# ESC.net
KiCad netlist of a schematic drawn in Altium Designer
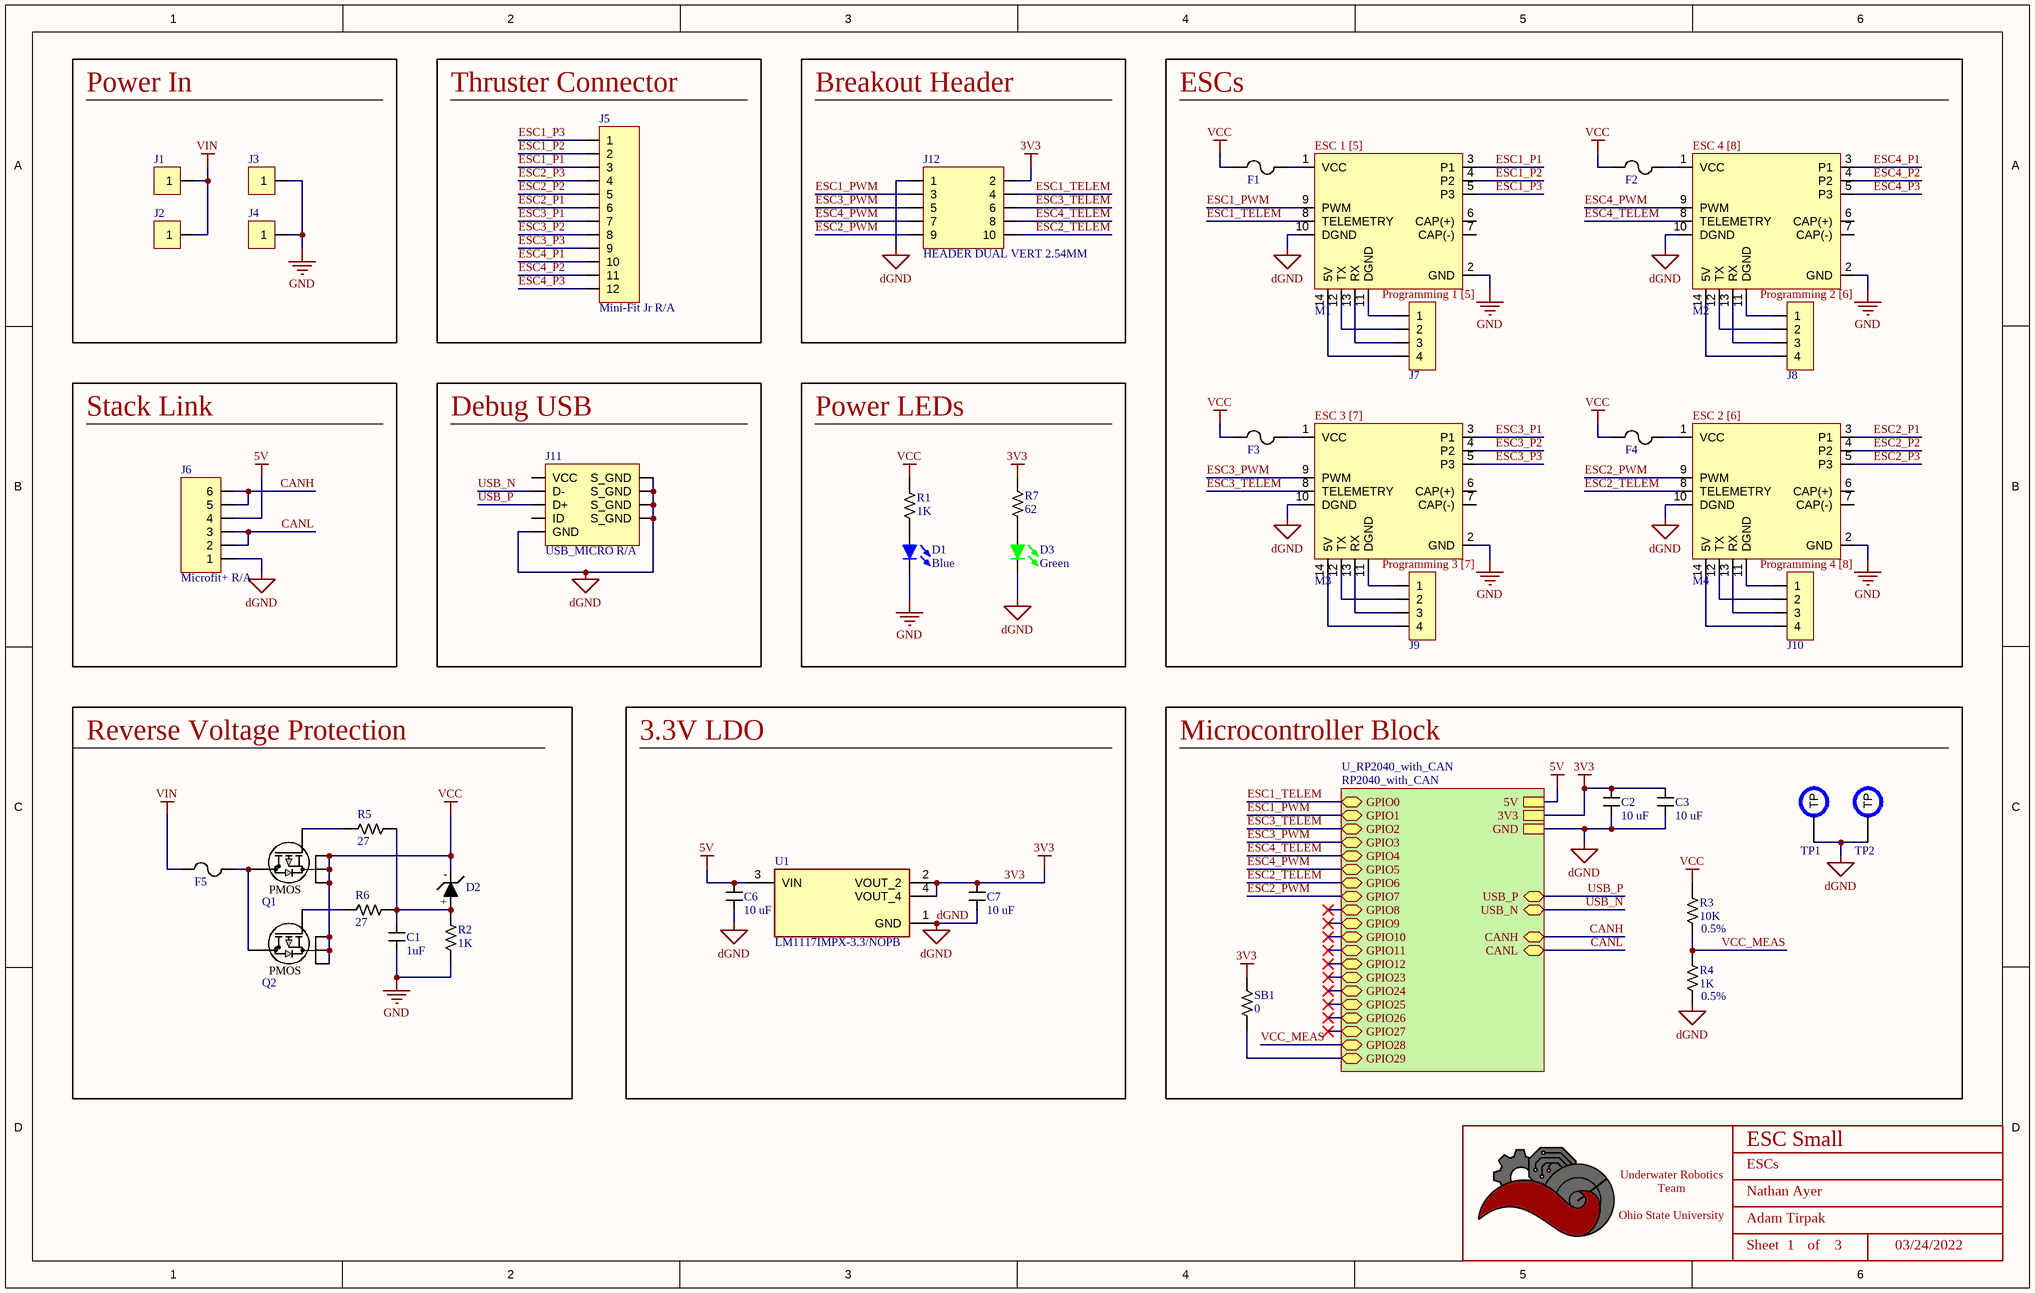
[diagram p0: ESC.SchDoc]

(export (version "E")
  (design (tool "Eeschema 10.0.6"))
  (components
    (comp (ref "*")
      (value "Title_Block")
      (footprint "LOGO")
      (description "UWRT Schematic Title Block Template\r\n\r\nCreated June 2021, Dylan Trainor")
      (libsource (lib "UWRT") (part "Title_Block"))
    )
    (comp (ref "C1")
      (value "1uF")
      (footprint "CAPACITOR_0603")
      (description "Cap 1uF 16V +/-10%\r\nCeramic 0603")
      (fields
        (field (name "TOLERANCE") "+/- 10%")
        (field (name "VOLTAGE") "16V")
        (field (name "MADE BY") "Flip B")
      )
      (libsource (lib "Capacitors") (part "CAPACITOR_1uF_0603"))
    )
    (comp (ref "C2")
      (value "10uF Ceramic 6.3V")
      (footprint "CAPACITOR_0603")
      (description "Cap 10uF 6.3V +/-20%\r\nCeramic 0603")
      (fields
        (field (name "TOLERANCE") "+/- 20%")
        (field (name "VOLTAGE") "6.3V")
        (field (name "VALUE (UF)") "10 uF")
        (field (name "MADE BY") "Flip B")
      )
      (libsource (lib "Capacitors") (part "CAPACITOR_10uF_0603"))
    )
    (comp (ref "C3")
      (value "10uF Ceramic 6.3V")
      (footprint "CAPACITOR_0603")
      (description "Cap 10uF 6.3V +/-20%\r\nCeramic 0603")
      (fields
        (field (name "TOLERANCE") "+/- 20%")
        (field (name "VOLTAGE") "6.3V")
        (field (name "VALUE (UF)") "10 uF")
        (field (name "MADE BY") "Flip B")
      )
      (libsource (lib "Capacitors") (part "CAPACITOR_10uF_0603"))
    )
    (comp (ref "C6")
      (value "10uF Ceramic 6.3V")
      (footprint "CAPACITOR_0603")
      (description "Cap 10uF 6.3V +/-20%\r\nCeramic 0603")
      (fields
        (field (name "TOLERANCE") "+/- 20%")
        (field (name "VOLTAGE") "6.3V")
        (field (name "VALUE (UF)") "10 uF")
        (field (name "MADE BY") "Flip B")
      )
      (libsource (lib "Capacitors") (part "CAPACITOR_10uF_0603"))
    )
    (comp (ref "C7")
      (value "10uF Ceramic 6.3V")
      (footprint "CAPACITOR_0603")
      (description "Cap 10uF 6.3V +/-20%\r\nCeramic 0603")
      (fields
        (field (name "TOLERANCE") "+/- 20%")
        (field (name "VOLTAGE") "6.3V")
        (field (name "VALUE (UF)") "10 uF")
        (field (name "MADE BY") "Flip B")
      )
      (libsource (lib "Capacitors") (part "CAPACITOR_10uF_0603"))
    )
    (comp (ref "D1")
      (value "150060BS75000")
      (footprint "LED_0603")
      (description "LED Blue Vf= 3.2V If = 0.020A\r\n150060BS75000")
      (fields (field (name "COLOR") "Blue") (field (name "MADE BY") "Robert Pafford"))
      (libsource (lib "Diodes") (part "LED_Blue_0603"))
    )
    (comp (ref "D2")
      (value "Zener_Diode_10V_410mW")
      (footprint "SOD-123")
      (description "Zener Diode ¦ 10 V ¦ 410 mW ¦ SOD 123")
      (fields (field (name "POWER") "410mW") (field (name "MADE BY") "Nathan A"))
      (libsource (lib "Diodes") (part "Zener_Diode_10V_410mW"))
    )
    (comp (ref "D3")
      (value "150060GS75000")
      (footprint "LED_0603")
      (description "LED Green Vf= 3.2V If = 0.025A\r\n150060GS75000")
      (fields (field (name "COLOR") "Green") (field (name "MADE BY") "Flip B"))
      (libsource (lib "Diodes") (part "LED_Green_0603_3.2V"))
    )
    (comp (ref "F1")
      (value "0685H9150-01")
      (footprint "0501Series_LTF")
      (description "Bel Fuse  ¦ 15A ¦ 32V DC ¦ SMD ¦ Fast Blow ¦ 1206")
      (fields (field (name "CREATED BY") "Nathan Ayer"))
      (libsource (lib "Fuses") (part "Bel Fuse 15A"))
    )
    (comp (ref "F2")
      (value "0685H9150-01")
      (footprint "0501Series_LTF")
      (description "Bel Fuse  ¦ 15A ¦ 32V DC ¦ SMD ¦ Fast Blow ¦ 1206")
      (fields (field (name "CREATED BY") "Nathan Ayer"))
      (libsource (lib "Fuses") (part "Bel Fuse 15A"))
    )
    (comp (ref "F3")
      (value "0685H9150-01")
      (footprint "0501Series_LTF")
      (description "Bel Fuse  ¦ 15A ¦ 32V DC ¦ SMD ¦ Fast Blow ¦ 1206")
      (fields (field (name "CREATED BY") "Nathan Ayer"))
      (libsource (lib "Fuses") (part "Bel Fuse 15A"))
    )
    (comp (ref "F4")
      (value "0685H9150-01")
      (footprint "0501Series_LTF")
      (description "Bel Fuse  ¦ 15A ¦ 32V DC ¦ SMD ¦ Fast Blow ¦ 1206")
      (fields (field (name "CREATED BY") "Nathan Ayer"))
      (libsource (lib "Fuses") (part "Bel Fuse 15A"))
    )
    (comp (ref "F5")
      (value "1245HC60-RTR")
      (footprint "2-SMD Fuse")
      (description "Eaton  ¦ 60A ¦ 80V DC ¦ SMD ¦ Fast Blow ¦ 2-SMD")
      (fields (field (name "CREATED BY") "Nathan Ayer"))
      (libsource (lib "Fuses") (part "Eaton 60A Fuse"))
    )
    (comp (ref "J1")
      (value "Redcube M4 Term 85A")
      (footprint "Redcube M4 Term 85A")
      (fields (field (name "CREATED BY") "Nahtan Ayer"))
      (libsource (lib "Connectors") (part "Redcube M4 Term 85A"))
    )
    (comp (ref "J2")
      (value "Redcube M4 Term 85A")
      (footprint "Redcube M4 Term 85A")
      (fields (field (name "CREATED BY") "Nahtan Ayer"))
      (libsource (lib "Connectors") (part "Redcube M4 Term 85A"))
    )
    (comp (ref "J3")
      (value "Redcube M4 Term 85A")
      (footprint "Redcube M4 Term 85A")
      (fields (field (name "CREATED BY") "Nahtan Ayer"))
      (libsource (lib "Connectors") (part "Redcube M4 Term 85A"))
    )
    (comp (ref "J4")
      (value "Redcube M4 Term 85A")
      (footprint "Redcube M4 Term 85A")
      (fields (field (name "CREATED BY") "Nahtan Ayer"))
      (libsource (lib "Connectors") (part "Redcube M4 Term 85A"))
    )
    (comp (ref "J5")
      (value "Mini-Fit Jr R/A")
      (footprint "CONN_MOLEX_MINIFIT JR_12 POS_R/A")
      (description "Molex Minifit Jr. 5569 \r\n12 Pos R/A Natural")
      (fields (field (name "MANUFACTURER") "Molex") (field (name "CREATED BY") "Flip B"))
      (libsource (lib "Connectors") (part "CONN_MOLEX_MINIFIT JR_12POS_R/A"))
    )
    (comp (ref "J6")
      (value "Microfit+ R/A")
      (footprint "CONN_MOLEX_MICROFIT+_6_POS_R/A")
      (description "Molex Microfit+ \r\n212528 6 POS R/A Black")
      (fields (field (name "MANUFACTURER") "Molex"))
      (libsource (lib "Connectors") (part "CONN_MOLEX_MICROFIT+_6POS_R/A"))
    )
    (comp (ref "J7")
      (value "HEADER VERT 2.54MM")
      (footprint "HEADER_4PIN_2.54MM")
      (description "CONN HEADER VERT 4POS 2.54MM")
      (fields (field (name "MADE BY") "Robert Pafford"))
      (libsource (lib "Connectors") (part "HEADER_4PIN_2.54MM"))
    )
    (comp (ref "J8")
      (value "HEADER VERT 2.54MM")
      (footprint "HEADER_4PIN_2.54MM")
      (description "CONN HEADER VERT 4POS 2.54MM")
      (fields (field (name "MADE BY") "Robert Pafford"))
      (libsource (lib "Connectors") (part "HEADER_4PIN_2.54MM"))
    )
    (comp (ref "J9")
      (value "HEADER VERT 2.54MM")
      (footprint "HEADER_4PIN_2.54MM")
      (description "CONN HEADER VERT 4POS 2.54MM")
      (fields (field (name "MADE BY") "Robert Pafford"))
      (libsource (lib "Connectors") (part "HEADER_4PIN_2.54MM"))
    )
    (comp (ref "J10")
      (value "HEADER VERT 2.54MM")
      (footprint "HEADER_4PIN_2.54MM")
      (description "CONN HEADER VERT 4POS 2.54MM")
      (fields (field (name "MADE BY") "Robert Pafford"))
      (libsource (lib "Connectors") (part "HEADER_4PIN_2.54MM"))
    )
    (comp (ref "J11")
      (value "USB_MICRO R/A")
      (footprint "CONN_MINIUSB")
      (description "Amphenol Micro USB-B\r\nUSB2.0 5 Pin Right Angle SMD")
      (fields (field (name "MANUFACTURER") "Amphenol") (field (name "CREATED BY") "Flip B"))
      (libsource (lib "Connectors") (part "CONN_MICROUSB"))
    )
    (comp (ref "J12")
      (value "HEADER DUAL VERT 2.54MM")
      (footprint "HEADER_2X5PIN_2.54MM")
      (description "CONN HEADER VERT 10POS 2.54MM")
      (fields (field (name "MADE BY") "Robert Pafford"))
      (libsource (lib "Connectors") (part "HEADER_2x5PIN_2.54MM"))
    )
    (comp (ref "M1")
      (value "APD 80F3[X]")
      (footprint "APD 80F3[X]")
      (description "Advanced Power Drives 80F3[X] ESC ¦ 15-35V ¦ 80A")
      (fields
        (field (name "VOLTAGE") "15-35V")
        (field (name "MANUFACTURER") "Advanced Power Drives")
        (field (name "CREATED BY") "Nathan Ayer")
      )
      (libsource (lib "Modules") (part "APD 80F3[X]"))
    )
    (comp (ref "M2")
      (value "APD 80F3[X]")
      (footprint "APD 80F3[X]")
      (description "Advanced Power Drives 80F3[X] ESC ¦ 15-35V ¦ 80A")
      (fields
        (field (name "VOLTAGE") "15-35V")
        (field (name "MANUFACTURER") "Advanced Power Drives")
        (field (name "CREATED BY") "Nathan Ayer")
      )
      (libsource (lib "Modules") (part "APD 80F3[X]"))
    )
    (comp (ref "M3")
      (value "APD 80F3[X]")
      (footprint "APD 80F3[X]")
      (description "Advanced Power Drives 80F3[X] ESC ¦ 15-35V ¦ 80A")
      (fields
        (field (name "VOLTAGE") "15-35V")
        (field (name "MANUFACTURER") "Advanced Power Drives")
        (field (name "CREATED BY") "Nathan Ayer")
      )
      (libsource (lib "Modules") (part "APD 80F3[X]"))
    )
    (comp (ref "M4")
      (value "APD 80F3[X]")
      (footprint "APD 80F3[X]")
      (description "Advanced Power Drives 80F3[X] ESC ¦ 15-35V ¦ 80A")
      (fields
        (field (name "VOLTAGE") "15-35V")
        (field (name "MANUFACTURER") "Advanced Power Drives")
        (field (name "CREATED BY") "Nathan Ayer")
      )
      (libsource (lib "Modules") (part "APD 80F3[X]"))
    )
    (comp (ref "Q1")
      (value "MOSFET P-Ch 30V 60A SO-8")
      (footprint "MOSFET_7DP-T1-GE3_VIS")
      (description "P-Channel 30 V 60A (Tc) 65.8W (Tc) Surface Mount PowerPAK® SO-8")
      (fields
        (field (name "MANUFACTURER_PART_NUMBER") "SIR167DP-T1-GE3")
        (field (name "COPYRIGHT") "Copyright (C) 2022 Ultra Librarian. All rights reserved.")
      )
      (libsource (lib "Transistors") (part "SIR167DP-T1-GE3"))
    )
    (comp (ref "Q2")
      (value "MOSFET P-Ch 30V 60A SO-8")
      (footprint "MOSFET_7DP-T1-GE3_VIS")
      (description "P-Channel 30 V 60A (Tc) 65.8W (Tc) Surface Mount PowerPAK® SO-8")
      (fields
        (field (name "MANUFACTURER_PART_NUMBER") "SIR167DP-T1-GE3")
        (field (name "COPYRIGHT") "Copyright (C) 2022 Ultra Librarian. All rights reserved.")
      )
      (libsource (lib "Transistors") (part "SIR167DP-T1-GE3"))
    )
    (comp (ref "R1")
      (value "1k Ohm 5% 1/8W")
      (footprint "RESISTOR_0603")
      (description "RES 1k OHM 5% 1/8W 0603")
      (fields
        (field (name "TOLERANCE") "+/- 5%")
        (field (name "VALUE  (OHMS)") "1K")
        (field (name "MADE BY") "Robert Pafford")
      )
      (libsource (lib "Resistors") (part "RESISTOR_1K_0603"))
    )
    (comp (ref "R2")
      (value "1k Ohm 5% 1/8W")
      (footprint "RESISTOR_0603")
      (description "RES 1k OHM 5% 1/8W 0603")
      (fields
        (field (name "TOLERANCE") "+/- 5%")
        (field (name "VALUE  (OHMS)") "1K")
        (field (name "MADE BY") "Robert Pafford")
      )
      (libsource (lib "Resistors") (part "RESISTOR_1K_0603"))
    )
    (comp (ref "R3")
      (value "10k Ohm 0.5% 1/10W")
      (footprint "RESISTOR_0603")
      (description "RES 10k OHM 0.5% 1/10W 0603")
      (fields
        (field (name "TOLERANCE") "+/- 0.5%")
        (field (name "VALUE  (OHMS)") "10K")
        (field (name "MADE BY") "Robert Pafford")
      )
      (libsource (lib "Resistors") (part "RESISTOR_10K_0.5%_0603"))
    )
    (comp (ref "R4")
      (value "1k Ohm 5% 1/10W")
      (footprint "RESISTOR_0603")
      (description "RES 1k OHM 0.5% 1/10W 0603")
      (fields
        (field (name "TOLERANCE") "+/- 0.5%")
        (field (name "VALUE  (OHMS)") "1K")
        (field (name "MADE BY") "Robert Pafford")
      )
      (libsource (lib "Resistors") (part "RESISTOR_1K_0.5%_0603"))
    )
    (comp (ref "R5")
      (value "27 Ohm 5% 1/8W")
      (footprint "RESISTOR_0603")
      (description "RES 27 OHM 5% 1/8W 0603")
      (fields
        (field (name "TOLERANCE") "+/- 5%")
        (field (name "VALUE  (OHMS)") "27")
        (field (name "MADE BY") "Robert Pafford")
      )
      (libsource (lib "Resistors") (part "RESISTOR_27_0603"))
    )
    (comp (ref "R6")
      (value "27 Ohm 5% 1/8W")
      (footprint "RESISTOR_0603")
      (description "RES 27 OHM 5% 1/8W 0603")
      (fields
        (field (name "TOLERANCE") "+/- 5%")
        (field (name "VALUE  (OHMS)") "27")
        (field (name "MADE BY") "Robert Pafford")
      )
      (libsource (lib "Resistors") (part "RESISTOR_27_0603"))
    )
    (comp (ref "R7")
      (value "62 Ohm 1% 1/4W")
      (footprint "RESISTOR_0603")
      (description "RES SMD 62 OHM 1% 1/4W 0603")
      (fields
        (field (name "TOLERANCE") "+/- 1%")
        (field (name "VALUE  (OHMS)") "62")
        (field (name "MADE BY") "Robert Pafford")
      )
      (libsource (lib "Resistors") (part "RESISTOR_62_0603"))
    )
    (comp (ref "SB1")
      (value "0 Ohm Jumper No Fit")
      (footprint "RESISTOR_0603")
      (description "0 Ohm Jumper No Fit for Solder Bridge")
      (fields (field (name "VALUE  (OHMS)") "0") (field (name "MADE BY") "Robert Pafford"))
      (libsource (lib "Resistors") (part "JUMPER_0_0603"))
    )
    (comp (ref "TP1")
      (value "PCB Test Point")
      (footprint "TESTPOINT_1.2MM")
      (fields (field (name "MADE BY") "Robert Pafford"))
      (libsource (lib "Connectors") (part "TESTPOINT"))
    )
    (comp (ref "TP2")
      (value "PCB Test Point")
      (footprint "TESTPOINT_1.2MM")
      (fields (field (name "MADE BY") "Robert Pafford"))
      (libsource (lib "Connectors") (part "TESTPOINT"))
    )
    (comp (ref "U1")
      (value "LM1117IMPX-3.3/NOPB")
      (footprint "SOT-223-4")
      (description "800-mA 15-V linear voltage regulator 4-SOT-223 -40 to 125")
      (fields (field (name "MF") "Texas Instruments"))
      (libsource (lib "Integrated Circuits") (part "LM1117IMPX-3.3/NOPB"))
    )
  )
  (nets
    (net (code "1") (name "/CANH") (class "Default")
      (node (ref "J6") (pin "5") (pinfunction "5_5") (pintype "passive"))
      (node (ref "J6") (pin "6") (pinfunction "6_6") (pintype "passive"))
    )
    (net (code "2") (name "/CANL") (class "Default")
      (node (ref "J6") (pin "2") (pinfunction "2_2") (pintype "passive"))
      (node (ref "J6") (pin "3") (pinfunction "3_3") (pintype "passive"))
    )
    (net (code "3") (name "/ESC1_P1") (class "Default")
      (node (ref "J5") (pin "3") (pinfunction "3_3") (pintype "passive"))
      (node (ref "M1") (pin "3") (pinfunction "P1_3") (pintype "passive"))
    )
    (net (code "4") (name "/ESC1_P2") (class "Default")
      (node (ref "J5") (pin "2") (pinfunction "2_2") (pintype "passive"))
      (node (ref "M1") (pin "4") (pinfunction "P2_4") (pintype "passive"))
    )
    (net (code "5") (name "/ESC1_P3") (class "Default")
      (node (ref "J5") (pin "1") (pinfunction "1_1") (pintype "passive"))
      (node (ref "M1") (pin "5") (pinfunction "P3_5") (pintype "passive"))
    )
    (net (code "6") (name "/ESC1_PWM") (class "Default")
      (node (ref "J12") (pin "3") (pinfunction "3_3") (pintype "passive"))
      (node (ref "M1") (pin "9") (pinfunction "PWM_9") (pintype "passive"))
    )
    (net (code "7") (name "/ESC1_TELEM") (class "Default")
      (node (ref "J12") (pin "4") (pinfunction "4_4") (pintype "passive"))
      (node (ref "M1") (pin "8") (pinfunction "TELEMETRY_8") (pintype "passive"))
    )
    (net (code "8") (name "/ESC2_P1") (class "Default")
      (node (ref "J5") (pin "6") (pinfunction "6_6") (pintype "passive"))
      (node (ref "M4") (pin "3") (pinfunction "P1_3") (pintype "passive"))
    )
    (net (code "9") (name "/ESC2_P2") (class "Default")
      (node (ref "J5") (pin "5") (pinfunction "5_5") (pintype "passive"))
      (node (ref "M4") (pin "4") (pinfunction "P2_4") (pintype "passive"))
    )
    (net (code "10") (name "/ESC2_P3") (class "Default")
      (node (ref "J5") (pin "4") (pinfunction "4_4") (pintype "passive"))
      (node (ref "M4") (pin "5") (pinfunction "P3_5") (pintype "passive"))
    )
    (net (code "11") (name "/ESC2_PWM") (class "Default")
      (node (ref "J12") (pin "9") (pinfunction "9_9") (pintype "passive"))
      (node (ref "M4") (pin "9") (pinfunction "PWM_9") (pintype "passive"))
    )
    (net (code "12") (name "/ESC2_TELEM") (class "Default")
      (node (ref "J12") (pin "10") (pinfunction "10_10") (pintype "passive"))
      (node (ref "M4") (pin "8") (pinfunction "TELEMETRY_8") (pintype "passive"))
    )
    (net (code "13") (name "/ESC3_P1") (class "Default")
      (node (ref "J5") (pin "7") (pinfunction "7_7") (pintype "passive"))
      (node (ref "M3") (pin "3") (pinfunction "P1_3") (pintype "passive"))
    )
    (net (code "14") (name "/ESC3_P2") (class "Default")
      (node (ref "J5") (pin "8") (pinfunction "8_8") (pintype "passive"))
      (node (ref "M3") (pin "4") (pinfunction "P2_4") (pintype "passive"))
    )
    (net (code "15") (name "/ESC3_P3") (class "Default")
      (node (ref "J5") (pin "9") (pinfunction "9_9") (pintype "passive"))
      (node (ref "M3") (pin "5") (pinfunction "P3_5") (pintype "passive"))
    )
    (net (code "16") (name "/ESC3_PWM") (class "Default")
      (node (ref "J12") (pin "5") (pinfunction "5_5") (pintype "passive"))
      (node (ref "M3") (pin "9") (pinfunction "PWM_9") (pintype "passive"))
    )
    (net (code "17") (name "/ESC3_TELEM") (class "Default")
      (node (ref "J12") (pin "6") (pinfunction "6_6") (pintype "passive"))
      (node (ref "M3") (pin "8") (pinfunction "TELEMETRY_8") (pintype "passive"))
    )
    (net (code "18") (name "/ESC4_P1") (class "Default")
      (node (ref "J5") (pin "10") (pinfunction "10_10") (pintype "passive"))
      (node (ref "M2") (pin "3") (pinfunction "P1_3") (pintype "passive"))
    )
    (net (code "19") (name "/ESC4_P2") (class "Default")
      (node (ref "J5") (pin "11") (pinfunction "11_11") (pintype "passive"))
      (node (ref "M2") (pin "4") (pinfunction "P2_4") (pintype "passive"))
    )
    (net (code "20") (name "/ESC4_P3") (class "Default")
      (node (ref "J5") (pin "12") (pinfunction "12_12") (pintype "passive"))
      (node (ref "M2") (pin "5") (pinfunction "P3_5") (pintype "passive"))
    )
    (net (code "21") (name "/ESC4_PWM") (class "Default")
      (node (ref "J12") (pin "7") (pinfunction "7_7") (pintype "passive"))
      (node (ref "M2") (pin "9") (pinfunction "PWM_9") (pintype "passive"))
    )
    (net (code "22") (name "/ESC4_TELEM") (class "Default")
      (node (ref "J12") (pin "8") (pinfunction "8_8") (pintype "passive"))
      (node (ref "M2") (pin "8") (pinfunction "TELEMETRY_8") (pintype "passive"))
    )
    (net (code "33") (name "/GPIO29") (class "Default")
      (node (ref "SB1") (pin "1") (pinfunction "1_1") (pintype "passive"))
    )
    (net (code "34") (name "/USB_N") (class "Default")
      (node (ref "J11") (pin "2") (pinfunction "D-_2") (pintype "passive"))
    )
    (net (code "35") (name "/USB_P") (class "Default")
      (node (ref "J11") (pin "3") (pinfunction "D+_3") (pintype "passive"))
    )
    (net (code "36") (name "/VCC_MEAS") (class "Default")
      (node (ref "R3") (pin "2") (pinfunction "2_2") (pintype "passive"))
      (node (ref "R4") (pin "1") (pinfunction "1_1") (pintype "passive"))
    )
    (net (code "37") (name "3V3") (class "Default")
      (node (ref "C2") (pin "1") (pinfunction "1_1") (pintype "passive"))
      (node (ref "C3") (pin "1") (pinfunction "1_1") (pintype "passive"))
      (node (ref "C7") (pin "1") (pinfunction "1_1") (pintype "passive"))
      (node (ref "J12") (pin "2") (pinfunction "2_2") (pintype "passive"))
      (node (ref "R7") (pin "2") (pinfunction "2_2") (pintype "passive"))
      (node (ref "SB1") (pin "2") (pinfunction "2_2") (pintype "passive"))
      (node (ref "U1") (pin "2") (pinfunction "VOUT_2_2") (pintype "power_in"))
      (node (ref "U1") (pin "4") (pinfunction "VOUT_4_4") (pintype "power_in"))
    )
    (net (code "38") (name "5V") (class "Default")
      (node (ref "C6") (pin "1") (pinfunction "1_1") (pintype "passive"))
      (node (ref "J6") (pin "4") (pinfunction "4_4") (pintype "passive"))
      (node (ref "U1") (pin "3") (pinfunction "VIN_3") (pintype "power_in"))
    )
    (net (code "39") (name "GND") (class "Default")
      (node (ref "C1") (pin "1") (pinfunction "1_1") (pintype "passive"))
      (node (ref "D1") (pin "2") (pinfunction "2_2") (pintype "passive"))
      (node (ref "J3") (pin "1") (pinfunction "1_1") (pintype "passive"))
      (node (ref "J4") (pin "1") (pinfunction "1_1") (pintype "passive"))
      (node (ref "M1") (pin "2") (pinfunction "GND_2") (pintype "passive"))
      (node (ref "M2") (pin "2") (pinfunction "GND_2") (pintype "passive"))
      (node (ref "M3") (pin "2") (pinfunction "GND_2") (pintype "passive"))
      (node (ref "M4") (pin "2") (pinfunction "GND_2") (pintype "passive"))
      (node (ref "R2") (pin "2") (pinfunction "2_2") (pintype "passive"))
    )
    (net (code "40") (name "Net-(C1-Pad2)") (class "Default")
      (node (ref "C1") (pin "2") (pinfunction "2_2") (pintype "passive"))
      (node (ref "D2") (pin "1") (pinfunction "1_1") (pintype "passive"))
      (node (ref "R2") (pin "1") (pinfunction "1_1") (pintype "passive"))
      (node (ref "R5") (pin "2") (pinfunction "2_2") (pintype "passive"))
      (node (ref "R6") (pin "1") (pinfunction "1_1") (pintype "passive"))
    )
    (net (code "41") (name "Net-(D1-Pad1)") (class "Default")
      (node (ref "D1") (pin "1") (pinfunction "1_1") (pintype "passive"))
      (node (ref "R1") (pin "2") (pinfunction "2_2") (pintype "passive"))
    )
    (net (code "42") (name "Net-(D3-Pad1)") (class "Default")
      (node (ref "D3") (pin "1") (pinfunction "1_1") (pintype "passive"))
      (node (ref "R7") (pin "1") (pinfunction "1_1") (pintype "passive"))
    )
    (net (code "43") (name "Net-(F5-Pad2)") (class "Default")
      (node (ref "F5") (pin "2") (pinfunction "2_2") (pintype "passive"))
      (node (ref "Q1") (pin "D") (pinfunction "D_D") (pintype "passive"))
      (node (ref "Q2") (pin "D") (pinfunction "D_D") (pintype "passive"))
    )
    (net (code "44") (name "Net-(J7-Pad1)") (class "Default")
      (node (ref "J7") (pin "1") (pinfunction "1_1") (pintype "passive"))
      (node (ref "M1") (pin "11") (pinfunction "DGND_11") (pintype "passive"))
    )
    (net (code "45") (name "Net-(J8-Pad1)") (class "Default")
      (node (ref "J8") (pin "1") (pinfunction "1_1") (pintype "passive"))
      (node (ref "M2") (pin "11") (pinfunction "DGND_11") (pintype "passive"))
    )
    (net (code "46") (name "Net-(J9-Pad1)") (class "Default")
      (node (ref "J9") (pin "1") (pinfunction "1_1") (pintype "passive"))
      (node (ref "M3") (pin "11") (pinfunction "DGND_11") (pintype "passive"))
    )
    (net (code "47") (name "Net-(J10-Pad1)") (class "Default")
      (node (ref "J10") (pin "1") (pinfunction "1_1") (pintype "passive"))
      (node (ref "M4") (pin "11") (pinfunction "DGND_11") (pintype "passive"))
    )
    (net (code "48") (name "Net-(M1-5V)") (class "Default")
      (node (ref "J7") (pin "4") (pinfunction "4_4") (pintype "passive"))
      (node (ref "M1") (pin "14") (pinfunction "5V_14") (pintype "passive"))
    )
    (net (code "49") (name "Net-(M1-RX)") (class "Default")
      (node (ref "J7") (pin "3") (pinfunction "3_3") (pintype "passive"))
      (node (ref "M1") (pin "13") (pinfunction "RX_13") (pintype "passive"))
    )
    (net (code "50") (name "Net-(M1-TX)") (class "Default")
      (node (ref "J7") (pin "2") (pinfunction "2_2") (pintype "passive"))
      (node (ref "M1") (pin "12") (pinfunction "TX_12") (pintype "passive"))
    )
    (net (code "51") (name "Net-(M1-VCC)") (class "Default")
      (node (ref "F1") (pin "2") (pinfunction "2_2") (pintype "passive"))
      (node (ref "M1") (pin "1") (pinfunction "VCC_1") (pintype "passive"))
    )
    (net (code "52") (name "Net-(M2-5V)") (class "Default")
      (node (ref "J8") (pin "4") (pinfunction "4_4") (pintype "passive"))
      (node (ref "M2") (pin "14") (pinfunction "5V_14") (pintype "passive"))
    )
    (net (code "53") (name "Net-(M2-RX)") (class "Default")
      (node (ref "J8") (pin "3") (pinfunction "3_3") (pintype "passive"))
      (node (ref "M2") (pin "13") (pinfunction "RX_13") (pintype "passive"))
    )
    (net (code "54") (name "Net-(M2-TX)") (class "Default")
      (node (ref "J8") (pin "2") (pinfunction "2_2") (pintype "passive"))
      (node (ref "M2") (pin "12") (pinfunction "TX_12") (pintype "passive"))
    )
    (net (code "55") (name "Net-(M2-VCC)") (class "Default")
      (node (ref "F2") (pin "2") (pinfunction "2_2") (pintype "passive"))
      (node (ref "M2") (pin "1") (pinfunction "VCC_1") (pintype "passive"))
    )
    (net (code "56") (name "Net-(M3-5V)") (class "Default")
      (node (ref "J9") (pin "4") (pinfunction "4_4") (pintype "passive"))
      (node (ref "M3") (pin "14") (pinfunction "5V_14") (pintype "passive"))
    )
    (net (code "57") (name "Net-(M3-RX)") (class "Default")
      (node (ref "J9") (pin "3") (pinfunction "3_3") (pintype "passive"))
      (node (ref "M3") (pin "13") (pinfunction "RX_13") (pintype "passive"))
    )
    (net (code "58") (name "Net-(M3-TX)") (class "Default")
      (node (ref "J9") (pin "2") (pinfunction "2_2") (pintype "passive"))
      (node (ref "M3") (pin "12") (pinfunction "TX_12") (pintype "passive"))
    )
    (net (code "59") (name "Net-(M3-VCC)") (class "Default")
      (node (ref "F3") (pin "2") (pinfunction "2_2") (pintype "passive"))
      (node (ref "M3") (pin "1") (pinfunction "VCC_1") (pintype "passive"))
    )
    (net (code "60") (name "Net-(M4-5V)") (class "Default")
      (node (ref "J10") (pin "4") (pinfunction "4_4") (pintype "passive"))
      (node (ref "M4") (pin "14") (pinfunction "5V_14") (pintype "passive"))
    )
    (net (code "61") (name "Net-(M4-RX)") (class "Default")
      (node (ref "J10") (pin "3") (pinfunction "3_3") (pintype "passive"))
      (node (ref "M4") (pin "13") (pinfunction "RX_13") (pintype "passive"))
    )
    (net (code "62") (name "Net-(M4-TX)") (class "Default")
      (node (ref "J10") (pin "2") (pinfunction "2_2") (pintype "passive"))
      (node (ref "M4") (pin "12") (pinfunction "TX_12") (pintype "passive"))
    )
    (net (code "63") (name "Net-(M4-VCC)") (class "Default")
      (node (ref "F4") (pin "2") (pinfunction "2_2") (pintype "passive"))
      (node (ref "M4") (pin "1") (pinfunction "VCC_1") (pintype "passive"))
    )
    (net (code "64") (name "Net-(Q1-G)") (class "Default")
      (node (ref "Q1") (pin "4") (pinfunction "G_4") (pintype "passive"))
      (node (ref "R5") (pin "1") (pinfunction "1_1") (pintype "passive"))
    )
    (net (code "65") (name "Net-(Q2-G)") (class "Default")
      (node (ref "Q2") (pin "4") (pinfunction "G_4") (pintype "passive"))
      (node (ref "R6") (pin "2") (pinfunction "2_2") (pintype "passive"))
    )
    (net (code "66") (name "VCC") (class "Default")
      (node (ref "D2") (pin "2") (pinfunction "2_2") (pintype "passive"))
      (node (ref "F1") (pin "1") (pinfunction "1_1") (pintype "passive"))
      (node (ref "F2") (pin "1") (pinfunction "1_1") (pintype "passive"))
      (node (ref "F3") (pin "1") (pinfunction "1_1") (pintype "passive"))
      (node (ref "F4") (pin "1") (pinfunction "1_1") (pintype "passive"))
      (node (ref "Q1") (pin "1") (pinfunction "S_1") (pintype "passive"))
      (node (ref "Q1") (pin "2") (pinfunction "S_2") (pintype "passive"))
      (node (ref "Q1") (pin "3") (pinfunction "S_3") (pintype "passive"))
      (node (ref "Q2") (pin "1") (pinfunction "S_1") (pintype "passive"))
      (node (ref "Q2") (pin "2") (pinfunction "S_2") (pintype "passive"))
      (node (ref "Q2") (pin "3") (pinfunction "S_3") (pintype "passive"))
      (node (ref "R1") (pin "1") (pinfunction "1_1") (pintype "passive"))
      (node (ref "R3") (pin "1") (pinfunction "1_1") (pintype "passive"))
    )
    (net (code "67") (name "VIN") (class "Default")
      (node (ref "F5") (pin "1") (pinfunction "1_1") (pintype "passive"))
      (node (ref "J1") (pin "1") (pinfunction "1_1") (pintype "passive"))
      (node (ref "J2") (pin "1") (pinfunction "1_1") (pintype "passive"))
    )
    (net (code "68") (name "dGND") (class "Default")
      (node (ref "C2") (pin "2") (pinfunction "2_2") (pintype "passive"))
      (node (ref "C3") (pin "2") (pinfunction "2_2") (pintype "passive"))
      (node (ref "C6") (pin "2") (pinfunction "2_2") (pintype "passive"))
      (node (ref "C7") (pin "2") (pinfunction "2_2") (pintype "passive"))
      (node (ref "D3") (pin "2") (pinfunction "2_2") (pintype "passive"))
      (node (ref "J11") (pin "5") (pinfunction "GND_5") (pintype "passive"))
      (node (ref "J11") (pin "6") (pinfunction "S_GND_6") (pintype "passive"))
      (node (ref "J11") (pin "7") (pinfunction "S_GND_7") (pintype "passive"))
      (node (ref "J11") (pin "8") (pinfunction "S_GND_8") (pintype "passive"))
      (node (ref "J11") (pin "9") (pinfunction "S_GND_9") (pintype "passive"))
      (node (ref "J12") (pin "1") (pinfunction "1_1") (pintype "passive"))
      (node (ref "J6") (pin "1") (pinfunction "1_1") (pintype "passive"))
      (node (ref "M1") (pin "10") (pinfunction "DGND_10") (pintype "passive"))
      (node (ref "M2") (pin "10") (pinfunction "DGND_10") (pintype "passive"))
      (node (ref "M3") (pin "10") (pinfunction "DGND_10") (pintype "passive"))
      (node (ref "M4") (pin "10") (pinfunction "DGND_10") (pintype "passive"))
      (node (ref "R4") (pin "2") (pinfunction "2_2") (pintype "passive"))
      (node (ref "TP1") (pin "TP") (pinfunction "TP_TP") (pintype "passive"))
      (node (ref "TP2") (pin "TP") (pinfunction "TP_TP") (pintype "passive"))
      (node (ref "U1") (pin "1") (pinfunction "GND_1") (pintype "power_in"))
    )
    (net (code "69") (name "unconnected-(J11-ID-Pad4)") (class "Default")
      (node (ref "J11") (pin "4") (pinfunction "ID_4") (pintype "passive"))
    )
    (net (code "70") (name "unconnected-(J11-VCC-Pad1)") (class "Default")
      (node (ref "J11") (pin "1") (pinfunction "VCC_1") (pintype "passive"))
    )
    (net (code "71") (name "unconnected-(M1-CAP(+)-Pad6)") (class "Default")
      (node (ref "M1") (pin "6") (pinfunction "CAP(+)_6") (pintype "passive"))
    )
    (net (code "72") (name "unconnected-(M1-CAP(-)-Pad7)") (class "Default")
      (node (ref "M1") (pin "7") (pinfunction "CAP(-)_7") (pintype "passive"))
    )
    (net (code "73") (name "unconnected-(M2-CAP(+)-Pad6)") (class "Default")
      (node (ref "M2") (pin "6") (pinfunction "CAP(+)_6") (pintype "passive"))
    )
    (net (code "74") (name "unconnected-(M2-CAP(-)-Pad7)") (class "Default")
      (node (ref "M2") (pin "7") (pinfunction "CAP(-)_7") (pintype "passive"))
    )
    (net (code "75") (name "unconnected-(M3-CAP(+)-Pad6)") (class "Default")
      (node (ref "M3") (pin "6") (pinfunction "CAP(+)_6") (pintype "passive"))
    )
    (net (code "76") (name "unconnected-(M3-CAP(-)-Pad7)") (class "Default")
      (node (ref "M3") (pin "7") (pinfunction "CAP(-)_7") (pintype "passive"))
    )
    (net (code "77") (name "unconnected-(M4-CAP(+)-Pad6)") (class "Default")
      (node (ref "M4") (pin "6") (pinfunction "CAP(+)_6") (pintype "passive"))
    )
    (net (code "78") (name "unconnected-(M4-CAP(-)-Pad7)") (class "Default")
      (node (ref "M4") (pin "7") (pinfunction "CAP(-)_7") (pintype "passive"))
    )
  )
)
